# Board1_DustCounter.net
KiCad netlist of a schematic drawn in EAGLE
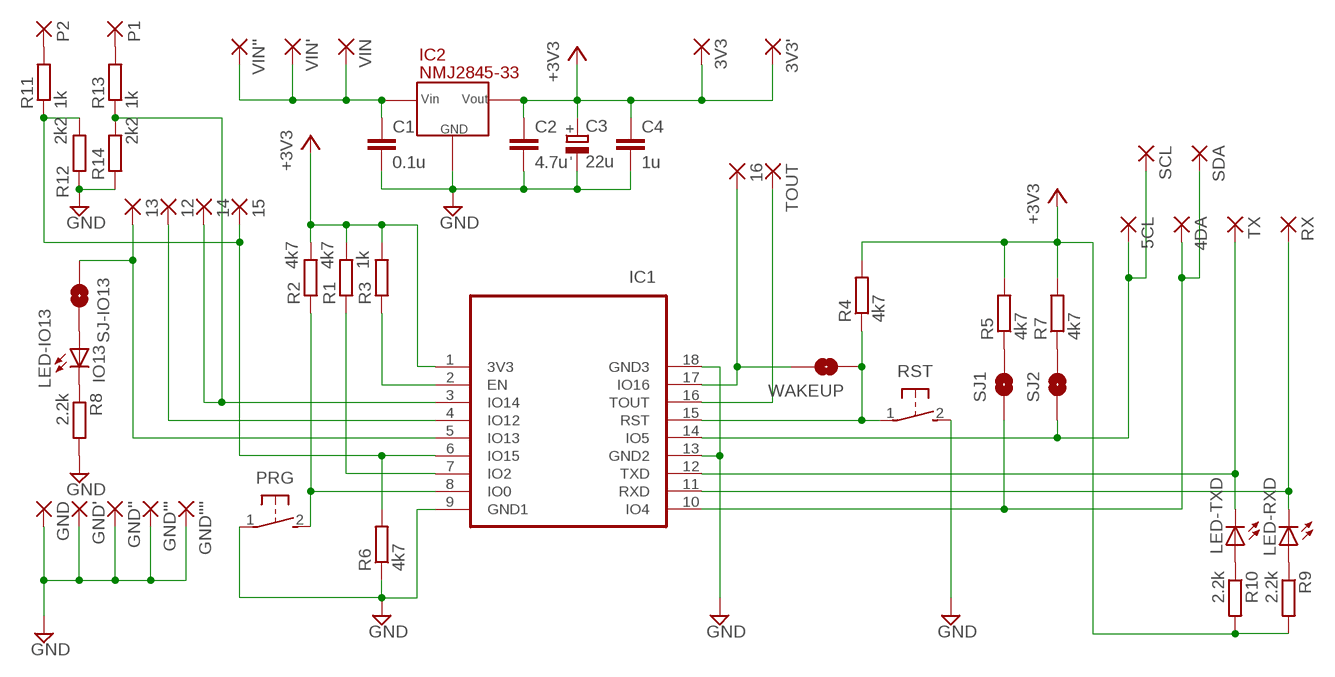
[diagram p0: schematic, sheet 1]

(export (version "E")
  (design (tool "Eeschema 10.0.6"))
  (components
    (comp (ref "3V3")
      (value "1,6/0,8")
      (footprint "eagle-import:1,6_0,8")
      (libsource (lib "eagle-import") (part "1,6/0,8"))
    )
    (comp (ref "3V3'")
      (value "1,6/0,8")
      (footprint "eagle-import:1,6_0,8")
      (libsource (lib "eagle-import") (part "1,6/0,8"))
    )
    (comp (ref "4DA")
      (value "1,6/0,8")
      (footprint "eagle-import:1,6_0,8")
      (libsource (lib "eagle-import") (part "1,6/0,8"))
    )
    (comp (ref "5CL")
      (value "1,6/0,8")
      (footprint "eagle-import:1,6_0,8")
      (libsource (lib "eagle-import") (part "1,6/0,8"))
    )
    (comp (ref "12")
      (value "1,6/0,8")
      (footprint "eagle-import:1,6_0,8")
      (libsource (lib "eagle-import") (part "1,6/0,8"))
    )
    (comp (ref "13")
      (value "1,6/0,8")
      (footprint "eagle-import:1,6_0,8")
      (libsource (lib "eagle-import") (part "1,6/0,8"))
    )
    (comp (ref "14")
      (value "1,6/0,8")
      (footprint "eagle-import:1,6_0,8")
      (libsource (lib "eagle-import") (part "1,6/0,8"))
    )
    (comp (ref "15")
      (value "1,6/0,8")
      (footprint "eagle-import:1,6_0,8")
      (libsource (lib "eagle-import") (part "1,6/0,8"))
    )
    (comp (ref "16")
      (value "1,6/0,8")
      (footprint "eagle-import:1,6_0,8")
      (libsource (lib "eagle-import") (part "1,6/0,8"))
    )
    (comp (ref "C1")
      (value "0.1u")
      (footprint "eagle-import:C0603")
      (libsource (lib "eagle-import") (part "C-EUC0603"))
    )
    (comp (ref "C2")
      (value "4.7u")
      (footprint "eagle-import:C0805")
      (libsource (lib "eagle-import") (part "resistor_C-EUC0805"))
    )
    (comp (ref "C3")
      (value "22u")
      (footprint "eagle-import:C6")
      (libsource (lib "eagle-import") (part "OS-CON/C6C"))
    )
    (comp (ref "C4")
      (value "1u")
      (footprint "eagle-import:C0603")
      (libsource (lib "eagle-import") (part "C-EUC0603"))
    )
    (comp (ref "GND")
      (value "1,6/0,8")
      (footprint "eagle-import:1,6_0,8")
      (libsource (lib "eagle-import") (part "1,6/0,8"))
    )
    (comp (ref "GND'")
      (value "1,6/0,8")
      (footprint "eagle-import:1,6_0,8")
      (libsource (lib "eagle-import") (part "1,6/0,8"))
    )
    (comp (ref "GND''")
      (value "1,6/0,8")
      (footprint "eagle-import:1,6_0,8")
      (libsource (lib "eagle-import") (part "1,6/0,8"))
    )
    (comp (ref "GND'''")
      (value "1,6/0,8")
      (footprint "eagle-import:1,6_0,8")
      (libsource (lib "eagle-import") (part "1,6/0,8"))
    )
    (comp (ref "GND''''")
      (value "1,6/0,8")
      (footprint "eagle-import:1,6_0,8")
      (libsource (lib "eagle-import") (part "1,6/0,8"))
    )
    (comp (ref "IC1")
      (value "ESP-WROOM-02FRONT-FACE")
      (footprint "eagle-import:FRONT-FACE")
      (libsource (lib "eagle-import") (part "ESP-WROOM-02FRONT-FACE"))
    )
    (comp (ref "IC2")
      (value "NMJ2845-33")
      (footprint "eagle-import:TO-252-3")
      (libsource (lib "eagle-import") (part "NJM2845DL1"))
    )
    (comp (ref "LED-IO13")
      (value "IO13")
      (footprint "eagle-import:CHIP-LED0603")
      (libsource (lib "eagle-import") (part "LEDCHIP-LED0603"))
    )
    (comp (ref "LED-RXD")
      (value "R")
      (footprint "eagle-import:CHIP-LED0603")
      (libsource (lib "eagle-import") (part "LEDCHIP-LED0603"))
    )
    (comp (ref "LED-TXD")
      (value "T")
      (footprint "eagle-import:CHIP-LED0603")
      (libsource (lib "eagle-import") (part "LEDCHIP-LED0603"))
    )
    (comp (ref "P1")
      (value "1,6/0,8")
      (footprint "eagle-import:1,6_0,8")
      (libsource (lib "eagle-import") (part "1,6/0,8"))
    )
    (comp (ref "P2")
      (value "1,6/0,8")
      (footprint "eagle-import:1,6_0,8")
      (libsource (lib "eagle-import") (part "1,6/0,8"))
    )
    (comp (ref "PRG")
      (value "SWITCH-TACTILESW")
      (footprint "eagle-import:SWITCH-TACTILE")
      (libsource (lib "eagle-import") (part "SWITCH-TACTILESW"))
    )
    (comp (ref "R1")
      (value "4k7")
      (footprint "eagle-import:R0603")
      (libsource (lib "eagle-import") (part "R-EU_R0603"))
    )
    (comp (ref "R2")
      (value "4k7")
      (footprint "eagle-import:R0603")
      (libsource (lib "eagle-import") (part "R-EU_R0603"))
    )
    (comp (ref "R3")
      (value "1k")
      (footprint "eagle-import:R0603")
      (libsource (lib "eagle-import") (part "R-EU_R0603"))
    )
    (comp (ref "R4")
      (value "4k7")
      (footprint "eagle-import:R0603")
      (libsource (lib "eagle-import") (part "R-EU_R0603"))
    )
    (comp (ref "R5")
      (value "4k7")
      (footprint "eagle-import:R0603")
      (libsource (lib "eagle-import") (part "R-EU_R0603"))
    )
    (comp (ref "R6")
      (value "4k7")
      (footprint "eagle-import:R0603")
      (libsource (lib "eagle-import") (part "R-EU_R0603"))
    )
    (comp (ref "R7")
      (value "4k7")
      (footprint "eagle-import:R0603")
      (libsource (lib "eagle-import") (part "R-EU_R0603"))
    )
    (comp (ref "R8")
      (value "2.2k")
      (footprint "eagle-import:R0603")
      (libsource (lib "eagle-import") (part "R-EU_R0603"))
    )
    (comp (ref "R9")
      (value "2.2k")
      (footprint "eagle-import:R0603")
      (libsource (lib "eagle-import") (part "R-EU_R0603"))
    )
    (comp (ref "R10")
      (value "2.2k")
      (footprint "eagle-import:R0603")
      (libsource (lib "eagle-import") (part "R-EU_R0603"))
    )
    (comp (ref "R11")
      (value "1k")
      (footprint "eagle-import:R0603")
      (libsource (lib "eagle-import") (part "R-EU_R0603"))
    )
    (comp (ref "R12")
      (value "2k2")
      (footprint "eagle-import:R0603")
      (libsource (lib "eagle-import") (part "R-EU_R0603"))
    )
    (comp (ref "R13")
      (value "1k")
      (footprint "eagle-import:R0603")
      (libsource (lib "eagle-import") (part "R-EU_R0603"))
    )
    (comp (ref "R14")
      (value "2k2")
      (footprint "eagle-import:R0603")
      (libsource (lib "eagle-import") (part "R-EU_R0603"))
    )
    (comp (ref "RST")
      (value "SWITCH-TACTILESW")
      (footprint "eagle-import:SWITCH-TACTILE")
      (libsource (lib "eagle-import") (part "SWITCH-TACTILESW"))
    )
    (comp (ref "RX")
      (value "1,6/0,8")
      (footprint "eagle-import:1,6_0,8")
      (libsource (lib "eagle-import") (part "1,6/0,8"))
    )
    (comp (ref "SCL")
      (value "1,6/0,8")
      (footprint "eagle-import:1,6_0,8")
      (libsource (lib "eagle-import") (part "1,6/0,8"))
    )
    (comp (ref "SDA")
      (value "1,6/0,8")
      (footprint "eagle-import:1,6_0,8")
      (libsource (lib "eagle-import") (part "1,6/0,8"))
    )
    (comp (ref "SJ-IO13")
      (value "SOLDERJUMPERNO")
      (footprint "eagle-import:SJ_2S-NO")
      (libsource (lib "eagle-import") (part "SOLDERJUMPERNO"))
    )
    (comp (ref "SJ1")
      (value "SDA/PU")
      (footprint "eagle-import:SJ_2S-NO")
      (libsource (lib "eagle-import") (part "SOLDERJUMPERNO"))
    )
    (comp (ref "SJ2")
      (value "SCL/PU")
      (footprint "eagle-import:SJ_2S-NO")
      (libsource (lib "eagle-import") (part "SOLDERJUMPERNO"))
    )
    (comp (ref "TOUT")
      (value "1,6/0,8")
      (footprint "eagle-import:1,6_0,8")
      (libsource (lib "eagle-import") (part "1,6/0,8"))
    )
    (comp (ref "TX")
      (value "1,6/0,8")
      (footprint "eagle-import:1,6_0,8")
      (libsource (lib "eagle-import") (part "1,6/0,8"))
    )
    (comp (ref "VIN")
      (value "1,6/0,8")
      (footprint "eagle-import:1,6_0,8")
      (libsource (lib "eagle-import") (part "1,6/0,8"))
    )
    (comp (ref "VIN'")
      (value "1,6/0,8")
      (footprint "eagle-import:1,6_0,8")
      (libsource (lib "eagle-import") (part "1,6/0,8"))
    )
    (comp (ref "VIN''")
      (value "1,6/0,8")
      (footprint "eagle-import:1,6_0,8")
      (libsource (lib "eagle-import") (part "1,6/0,8"))
    )
    (comp (ref "WAKEUP")
      (value "SOLDERJUMPERNO")
      (footprint "eagle-import:SJ_2S-NO")
      (libsource (lib "eagle-import") (part "SOLDERJUMPERNO"))
    )
  )
  (nets
    (net (code "1") (name "+3V3") (class "Default")
      (node (ref "3V3") (pin "1") (pinfunction "P_1") (pintype "passive"))
      (node (ref "3V3'") (pin "1") (pinfunction "P_1") (pintype "passive"))
      (node (ref "C2") (pin "1") (pinfunction "1_1") (pintype "passive"))
      (node (ref "C3") (pin "+") (pinfunction "+_+") (pintype "passive"))
      (node (ref "C4") (pin "1") (pinfunction "1_1") (pintype "passive"))
      (node (ref "IC1") (pin "1") (pinfunction "3V3_1") (pintype "power_in"))
      (node (ref "IC2") (pin "VOUT") (pinfunction "VOUT_VOUT") (pintype "power_in"))
      (node (ref "R1") (pin "2") (pinfunction "2_2") (pintype "passive"))
      (node (ref "R10") (pin "2") (pinfunction "2_2") (pintype "passive"))
      (node (ref "R2") (pin "2") (pinfunction "2_2") (pintype "passive"))
      (node (ref "R3") (pin "2") (pinfunction "2_2") (pintype "passive"))
      (node (ref "R4") (pin "2") (pinfunction "2_2") (pintype "passive"))
      (node (ref "R5") (pin "2") (pinfunction "2_2") (pintype "passive"))
      (node (ref "R7") (pin "2") (pinfunction "2_2") (pintype "passive"))
      (node (ref "R9") (pin "2") (pinfunction "2_2") (pintype "passive"))
    )
    (net (code "2") (name "GND") (class "Default")
      (node (ref "C1") (pin "2") (pinfunction "2_2") (pintype "passive"))
      (node (ref "C2") (pin "2") (pinfunction "2_2") (pintype "passive"))
      (node (ref "C3") (pin "-") (pinfunction "-_-") (pintype "passive"))
      (node (ref "C4") (pin "2") (pinfunction "2_2") (pintype "passive"))
      (node (ref "GND") (pin "1") (pinfunction "P_1") (pintype "passive"))
      (node (ref "GND'") (pin "1") (pinfunction "P_1") (pintype "passive"))
      (node (ref "GND''") (pin "1") (pinfunction "P_1") (pintype "passive"))
      (node (ref "GND'''") (pin "1") (pinfunction "P_1") (pintype "passive"))
      (node (ref "GND''''") (pin "1") (pinfunction "P_1") (pintype "passive"))
      (node (ref "IC1") (pin "13") (pinfunction "GND2_13") (pintype "power_in"))
      (node (ref "IC1") (pin "18") (pinfunction "GND3_18") (pintype "power_in"))
      (node (ref "IC1") (pin "9") (pinfunction "GND1_9") (pintype "power_in"))
      (node (ref "IC2") (pin "GND") (pinfunction "GND_GND") (pintype "power_in"))
      (node (ref "PRG") (pin "1") (pinfunction "1_1") (pintype "passive"))
      (node (ref "R12") (pin "1") (pinfunction "1_1") (pintype "passive"))
      (node (ref "R14") (pin "1") (pinfunction "1_1") (pintype "passive"))
      (node (ref "R6") (pin "1") (pinfunction "1_1") (pintype "passive"))
      (node (ref "R8") (pin "2") (pinfunction "2_2") (pintype "passive"))
      (node (ref "RST") (pin "2") (pinfunction "2_2") (pintype "passive"))
    )
    (net (code "3") (name "Net-(4DA-P)") (class "Default")
      (node (ref "4DA") (pin "1") (pinfunction "P_1") (pintype "passive"))
      (node (ref "IC1") (pin "10") (pinfunction "IO4_10") (pintype "bidirectional"))
      (node (ref "SDA") (pin "1") (pinfunction "P_1") (pintype "passive"))
      (node (ref "SJ1") (pin "1") (pinfunction "1_1") (pintype "passive"))
    )
    (net (code "4") (name "Net-(5CL-P)") (class "Default")
      (node (ref "5CL") (pin "1") (pinfunction "P_1") (pintype "passive"))
      (node (ref "IC1") (pin "14") (pinfunction "IO5_14") (pintype "open_collector"))
      (node (ref "SCL") (pin "1") (pinfunction "P_1") (pintype "passive"))
      (node (ref "SJ2") (pin "1") (pinfunction "1_1") (pintype "passive"))
    )
    (net (code "5") (name "Net-(12-P)") (class "Default")
      (node (ref "12") (pin "1") (pinfunction "P_1") (pintype "passive"))
      (node (ref "IC1") (pin "4") (pinfunction "IO12_4") (pintype "bidirectional"))
    )
    (net (code "6") (name "Net-(13-P)") (class "Default")
      (node (ref "13") (pin "1") (pinfunction "P_1") (pintype "passive"))
      (node (ref "IC1") (pin "5") (pinfunction "IO13_5") (pintype "bidirectional"))
      (node (ref "SJ-IO13") (pin "1") (pinfunction "1_1") (pintype "passive"))
    )
    (net (code "7") (name "Net-(14-P)") (class "Default")
      (node (ref "14") (pin "1") (pinfunction "P_1") (pintype "passive"))
      (node (ref "IC1") (pin "3") (pinfunction "IO14_3") (pintype "bidirectional"))
      (node (ref "R13") (pin "1") (pinfunction "1_1") (pintype "passive"))
      (node (ref "R14") (pin "2") (pinfunction "2_2") (pintype "passive"))
    )
    (net (code "8") (name "Net-(15-P)") (class "Default")
      (node (ref "15") (pin "1") (pinfunction "P_1") (pintype "passive"))
      (node (ref "IC1") (pin "6") (pinfunction "IO15_6") (pintype "bidirectional"))
      (node (ref "R11") (pin "1") (pinfunction "1_1") (pintype "passive"))
      (node (ref "R12") (pin "2") (pinfunction "2_2") (pintype "passive"))
      (node (ref "R6") (pin "2") (pinfunction "2_2") (pintype "passive"))
    )
    (net (code "9") (name "Net-(16-P)") (class "Default")
      (node (ref "16") (pin "1") (pinfunction "P_1") (pintype "passive"))
      (node (ref "IC1") (pin "17") (pinfunction "IO16_17") (pintype "bidirectional"))
      (node (ref "WAKEUP") (pin "2") (pinfunction "2_2") (pintype "passive"))
    )
    (net (code "10") (name "Net-(IC1-EN)") (class "Default")
      (node (ref "IC1") (pin "2") (pinfunction "EN_2") (pintype "bidirectional"))
      (node (ref "R3") (pin "1") (pinfunction "1_1") (pintype "passive"))
    )
    (net (code "11") (name "Net-(IC1-IO0)") (class "Default")
      (node (ref "IC1") (pin "8") (pinfunction "IO0_8") (pintype "bidirectional"))
      (node (ref "PRG") (pin "2") (pinfunction "2_2") (pintype "passive"))
      (node (ref "R2") (pin "1") (pinfunction "1_1") (pintype "passive"))
    )
    (net (code "12") (name "Net-(IC1-IO2)") (class "Default")
      (node (ref "IC1") (pin "7") (pinfunction "IO2_7") (pintype "bidirectional"))
      (node (ref "R1") (pin "1") (pinfunction "1_1") (pintype "passive"))
    )
    (net (code "13") (name "Net-(IC1-RST)") (class "Default")
      (node (ref "IC1") (pin "15") (pinfunction "RST_15") (pintype "bidirectional"))
      (node (ref "R4") (pin "1") (pinfunction "1_1") (pintype "passive"))
      (node (ref "RST") (pin "1") (pinfunction "1_1") (pintype "passive"))
      (node (ref "WAKEUP") (pin "1") (pinfunction "1_1") (pintype "passive"))
    )
    (net (code "14") (name "Net-(IC1-RXD)") (class "Default")
      (node (ref "IC1") (pin "11") (pinfunction "RXD_11") (pintype "bidirectional"))
      (node (ref "LED-RXD") (pin "C") (pinfunction "C_C") (pintype "passive"))
      (node (ref "RX") (pin "1") (pinfunction "P_1") (pintype "passive"))
    )
    (net (code "15") (name "Net-(IC1-TOUT)") (class "Default")
      (node (ref "IC1") (pin "16") (pinfunction "TOUT_16") (pintype "bidirectional"))
      (node (ref "TOUT") (pin "1") (pinfunction "P_1") (pintype "passive"))
    )
    (net (code "16") (name "Net-(IC1-TXD)") (class "Default")
      (node (ref "IC1") (pin "12") (pinfunction "TXD_12") (pintype "bidirectional"))
      (node (ref "LED-TXD") (pin "C") (pinfunction "C_C") (pintype "passive"))
      (node (ref "TX") (pin "1") (pinfunction "P_1") (pintype "passive"))
    )
    (net (code "17") (name "Net-(LED-IO13-PadA)") (class "Default")
      (node (ref "LED-IO13") (pin "A") (pinfunction "A_A") (pintype "passive"))
      (node (ref "SJ-IO13") (pin "2") (pinfunction "2_2") (pintype "passive"))
    )
    (net (code "18") (name "Net-(LED-IO13-PadC)") (class "Default")
      (node (ref "LED-IO13") (pin "C") (pinfunction "C_C") (pintype "passive"))
      (node (ref "R8") (pin "1") (pinfunction "1_1") (pintype "passive"))
    )
    (net (code "19") (name "Net-(LED-RXD-PadA)") (class "Default")
      (node (ref "LED-RXD") (pin "A") (pinfunction "A_A") (pintype "passive"))
      (node (ref "R9") (pin "1") (pinfunction "1_1") (pintype "passive"))
    )
    (net (code "20") (name "Net-(LED-TXD-PadA)") (class "Default")
      (node (ref "LED-TXD") (pin "A") (pinfunction "A_A") (pintype "passive"))
      (node (ref "R10") (pin "1") (pinfunction "1_1") (pintype "passive"))
    )
    (net (code "21") (name "Net-(P1-P)") (class "Default")
      (node (ref "P1") (pin "1") (pinfunction "P_1") (pintype "passive"))
      (node (ref "R13") (pin "2") (pinfunction "2_2") (pintype "passive"))
    )
    (net (code "22") (name "Net-(P2-P)") (class "Default")
      (node (ref "P2") (pin "1") (pinfunction "P_1") (pintype "passive"))
      (node (ref "R11") (pin "2") (pinfunction "2_2") (pintype "passive"))
    )
    (net (code "23") (name "Net-(R5-Pad1)") (class "Default")
      (node (ref "R5") (pin "1") (pinfunction "1_1") (pintype "passive"))
      (node (ref "SJ1") (pin "2") (pinfunction "2_2") (pintype "passive"))
    )
    (net (code "24") (name "Net-(R7-Pad1)") (class "Default")
      (node (ref "R7") (pin "1") (pinfunction "1_1") (pintype "passive"))
      (node (ref "SJ2") (pin "2") (pinfunction "2_2") (pintype "passive"))
    )
    (net (code "25") (name "Net-(VIN''-P)") (class "Default")
      (node (ref "C1") (pin "1") (pinfunction "1_1") (pintype "passive"))
      (node (ref "IC2") (pin "VIN") (pinfunction "VIN_VIN") (pintype "power_in"))
      (node (ref "VIN") (pin "1") (pinfunction "P_1") (pintype "passive"))
      (node (ref "VIN'") (pin "1") (pinfunction "P_1") (pintype "passive"))
      (node (ref "VIN''") (pin "1") (pinfunction "P_1") (pintype "passive"))
    )
  )
)
